# Gyroscope_Motion_Sensor.net
KiCad netlist of a schematic drawn in Altium Designer
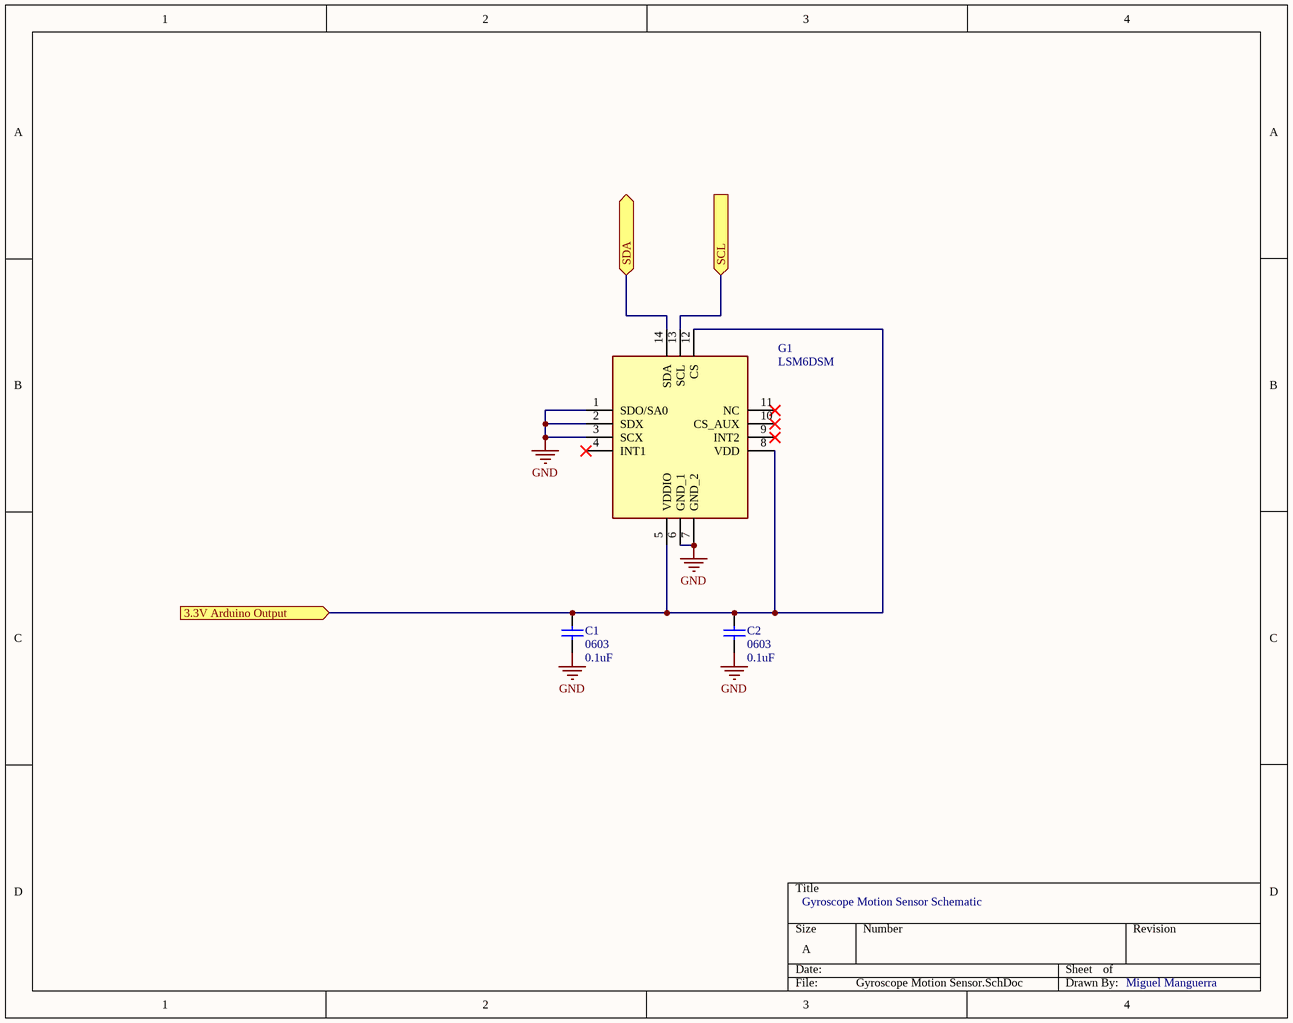
[diagram p0: Gyroscope Motion Sensor.SchDoc]

(export (version "E")
  (design (tool "Eeschema 10.0.6"))
  (components
    (comp (ref "C1")
      (value "0603")
      (footprint "SMD-0603C")
      (description "Capacitor")
      (fields (field (name "ALTIUM_VALUE") "0.1uF") (field (name "PUBLISHER") "Altium Limited"))
      (libsource (lib "Miscellaneous Devices") (part "Cap"))
    )
    (comp (ref "C2")
      (value "0603")
      (footprint "SMD-0603C")
      (description "Capacitor")
      (fields (field (name "ALTIUM_VALUE") "0.1uF") (field (name "PUBLISHER") "Altium Limited"))
      (libsource (lib "Miscellaneous Devices") (part "Cap"))
    )
    (comp (ref "G1")
      (value "LSM6DSM")
      (footprint "LGA-14(2.5X3X0.86)")
      (description "Integrated Circuit")
      (fields
        (field (name "MANUFACTURER_PART_NUMBER") "LSM6DS3HTR")
        (field (name "MOUSER PART NUMBER") "511-LSM6DS3HTR")
      )
      (libsource (lib "*") (part "LSM6DS3HTR"))
    )
  )
  (nets
    (net (code "1") (name "/3.3V Arduino Output") (class "Default")
      (node (ref "C1") (pin "2") (pinfunction "2_2") (pintype "passive"))
      (node (ref "C2") (pin "2") (pinfunction "2_2") (pintype "passive"))
      (node (ref "G1") (pin "12") (pinfunction "CS_12") (pintype "passive"))
      (node (ref "G1") (pin "5") (pinfunction "VDDIO_5") (pintype "passive"))
      (node (ref "G1") (pin "8") (pinfunction "VDD_8") (pintype "passive"))
    )
    (net (code "2") (name "/SCL") (class "Default")
      (node (ref "G1") (pin "13") (pinfunction "SCL_13") (pintype "passive"))
    )
    (net (code "3") (name "/SDA") (class "Default")
      (node (ref "G1") (pin "14") (pinfunction "SDA_14") (pintype "passive"))
    )
    (net (code "4") (name "GND") (class "Default")
      (node (ref "C1") (pin "1") (pinfunction "1_1") (pintype "passive"))
      (node (ref "C2") (pin "1") (pinfunction "1_1") (pintype "passive"))
      (node (ref "G1") (pin "1") (pinfunction "SDO/SA0_1") (pintype "passive"))
      (node (ref "G1") (pin "2") (pinfunction "SDX_2") (pintype "passive"))
      (node (ref "G1") (pin "3") (pinfunction "SCX_3") (pintype "passive"))
      (node (ref "G1") (pin "6") (pinfunction "GND_1_6") (pintype "passive"))
      (node (ref "G1") (pin "7") (pinfunction "GND_2_7") (pintype "passive"))
    )
    (net (code "5") (name "unconnected-(G1-CS_AUX-Pad10)") (class "Default")
      (node (ref "G1") (pin "10") (pinfunction "CS_AUX_10") (pintype "passive+no_connect"))
    )
    (net (code "6") (name "unconnected-(G1-INT1-Pad4)") (class "Default")
      (node (ref "G1") (pin "4") (pinfunction "INT1_4") (pintype "passive+no_connect"))
    )
    (net (code "7") (name "unconnected-(G1-INT2-Pad9)") (class "Default")
      (node (ref "G1") (pin "9") (pinfunction "INT2_9") (pintype "passive+no_connect"))
    )
    (net (code "8") (name "unconnected-(G1-NC-Pad11)") (class "Default")
      (node (ref "G1") (pin "11") (pinfunction "NC_11") (pintype "passive+no_connect"))
    )
  )
)
